# ESP12-breakout-smt-rev2.net
KiCad netlist of a schematic drawn in EAGLE
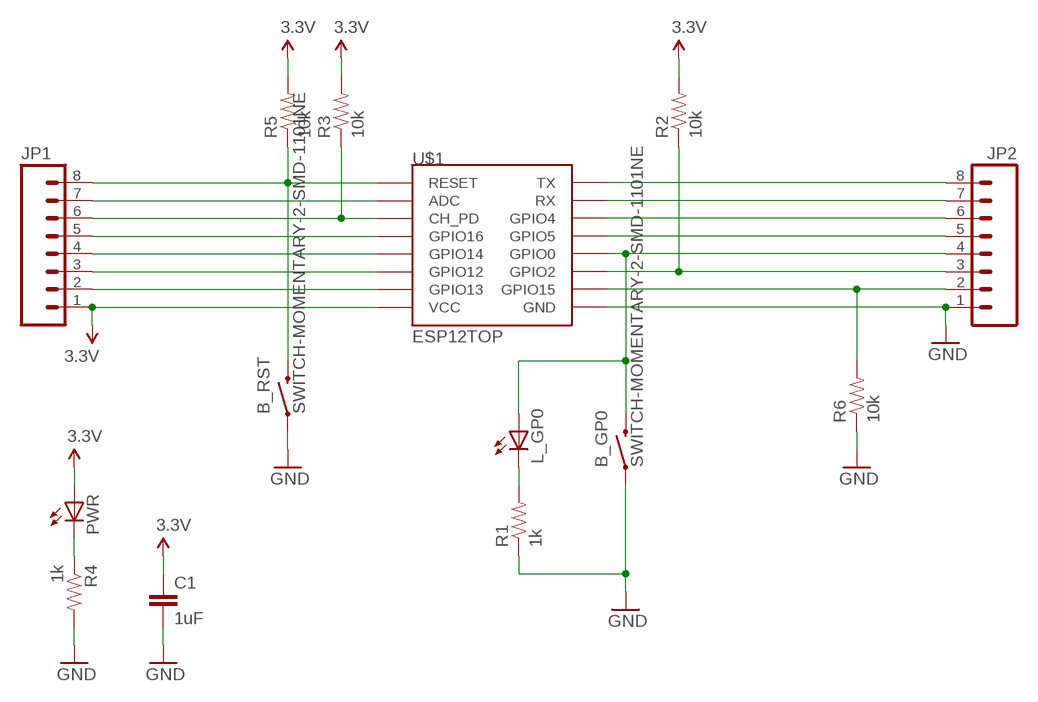
[diagram p0: schematic, sheet 1]

(export (version "E")
  (design (tool "Eeschema 10.0.6"))
  (components
    (comp (ref "B_GP0")
      (value "SWITCH-MOMENTARY-2-SMD-1101NE")
      (footprint "eagle-import:TACTILE-SWITCH-1101NE")
      (libsource (lib "eagle-import") (part "SWITCH-MOMENTARY-2-SMD-1101NE"))
    )
    (comp (ref "B_RST")
      (value "SWITCH-MOMENTARY-2-SMD-1101NE")
      (footprint "eagle-import:TACTILE-SWITCH-1101NE")
      (libsource (lib "eagle-import") (part "SWITCH-MOMENTARY-2-SMD-1101NE"))
    )
    (comp (ref "C1")
      (value "1uF")
      (footprint "eagle-import:0805")
      (libsource (lib "eagle-import") (part "CAP0805"))
    )
    (comp (ref "JP1")
      (value "M08")
      (footprint "eagle-import:1X08_PIN1_NO_SILK")
      (libsource (lib "eagle-import") (part "M08"))
    )
    (comp (ref "JP2")
      (value "M08")
      (footprint "eagle-import:1X08_PIN1_NO_SILK")
      (libsource (lib "eagle-import") (part "M08"))
    )
    (comp (ref "L_GP0")
      (value "LEDCHIPLED_0805")
      (footprint "eagle-import:CHIPLED_0805")
      (libsource (lib "eagle-import") (part "LEDCHIPLED_0805"))
    )
    (comp (ref "PWR")
      (value "LEDCHIPLED_0805")
      (footprint "eagle-import:CHIPLED_0805")
      (libsource (lib "eagle-import") (part "LEDCHIPLED_0805"))
    )
    (comp (ref "R1")
      (value "1k")
      (footprint "eagle-import:0603-RES")
      (libsource (lib "eagle-import") (part "RESISTOR0603"))
    )
    (comp (ref "R2")
      (value "10k")
      (footprint "eagle-import:0603-RES")
      (libsource (lib "eagle-import") (part "RESISTOR0603"))
    )
    (comp (ref "R3")
      (value "10k")
      (footprint "eagle-import:0603-RES")
      (libsource (lib "eagle-import") (part "RESISTOR0603"))
    )
    (comp (ref "R4")
      (value "1k")
      (footprint "eagle-import:0603-RES")
      (libsource (lib "eagle-import") (part "RESISTOR0603"))
    )
    (comp (ref "R5")
      (value "10k")
      (footprint "eagle-import:0603-RES")
      (libsource (lib "eagle-import") (part "RESISTOR0603"))
    )
    (comp (ref "R6")
      (value "10k")
      (footprint "eagle-import:0603-RES")
      (libsource (lib "eagle-import") (part "RESISTOR0603"))
    )
    (comp (ref "U$1")
      (value "ESP12TOP")
      (footprint "eagle-import:ESP12TOP")
      (libsource (lib "eagle-import") (part "ESP12TOP"))
    )
  )
  (nets
    (net (code "1") (name "3.3V") (class "Default")
      (node (ref "C1") (pin "1") (pinfunction "1_1") (pintype "passive"))
      (node (ref "JP1") (pin "1") (pinfunction "1_1") (pintype "passive"))
      (node (ref "PWR") (pin "A") (pinfunction "A_A") (pintype "passive"))
      (node (ref "R2") (pin "2") (pinfunction "2_2") (pintype "passive"))
      (node (ref "R3") (pin "2") (pinfunction "2_2") (pintype "passive"))
      (node (ref "R5") (pin "2") (pinfunction "2_2") (pintype "passive"))
      (node (ref "U$1") (pin "VCC") (pinfunction "VCC_VCC") (pintype "bidirectional"))
    )
    (net (code "2") (name "GND") (class "Default")
      (node (ref "B_GP0") (pin "1") (pinfunction "1_1") (pintype "passive"))
      (node (ref "B_RST") (pin "1") (pinfunction "1_1") (pintype "passive"))
      (node (ref "C1") (pin "2") (pinfunction "2_2") (pintype "passive"))
      (node (ref "JP2") (pin "1") (pinfunction "1_1") (pintype "passive"))
      (node (ref "R1") (pin "1") (pinfunction "1_1") (pintype "passive"))
      (node (ref "R4") (pin "2") (pinfunction "2_2") (pintype "passive"))
      (node (ref "R6") (pin "1") (pinfunction "1_1") (pintype "passive"))
      (node (ref "U$1") (pin "GND") (pinfunction "GND_GND") (pintype "bidirectional"))
    )
    (net (code "3") (name "Net-(B_GP0-Pad2)") (class "Default")
      (node (ref "B_GP0") (pin "2") (pinfunction "2_2") (pintype "passive"))
      (node (ref "JP2") (pin "4") (pinfunction "4_4") (pintype "passive"))
      (node (ref "L_GP0") (pin "A") (pinfunction "A_A") (pintype "passive"))
      (node (ref "U$1") (pin "GPIO0") (pinfunction "GPIO0_GPIO0") (pintype "bidirectional"))
    )
    (net (code "4") (name "Net-(B_RST-Pad2)") (class "Default")
      (node (ref "B_RST") (pin "2") (pinfunction "2_2") (pintype "passive"))
      (node (ref "JP1") (pin "8") (pinfunction "8_8") (pintype "passive"))
      (node (ref "R5") (pin "1") (pinfunction "1_1") (pintype "passive"))
      (node (ref "U$1") (pin "RESET") (pinfunction "RESET_RESET") (pintype "bidirectional"))
    )
    (net (code "5") (name "Net-(JP1-Pad2)") (class "Default")
      (node (ref "JP1") (pin "2") (pinfunction "2_2") (pintype "passive"))
      (node (ref "U$1") (pin "GPIO13") (pinfunction "GPIO13_GPIO13") (pintype "bidirectional"))
    )
    (net (code "6") (name "Net-(JP1-Pad3)") (class "Default")
      (node (ref "JP1") (pin "3") (pinfunction "3_3") (pintype "passive"))
      (node (ref "U$1") (pin "GPIO12") (pinfunction "GPIO12_GPIO12") (pintype "bidirectional"))
    )
    (net (code "7") (name "Net-(JP1-Pad4)") (class "Default")
      (node (ref "JP1") (pin "4") (pinfunction "4_4") (pintype "passive"))
      (node (ref "U$1") (pin "GPIO14") (pinfunction "GPIO14_GPIO14") (pintype "bidirectional"))
    )
    (net (code "8") (name "Net-(JP1-Pad5)") (class "Default")
      (node (ref "JP1") (pin "5") (pinfunction "5_5") (pintype "passive"))
      (node (ref "U$1") (pin "GPIO16") (pinfunction "GPIO16_GPIO16") (pintype "bidirectional"))
    )
    (net (code "9") (name "Net-(JP1-Pad6)") (class "Default")
      (node (ref "JP1") (pin "6") (pinfunction "6_6") (pintype "passive"))
      (node (ref "R3") (pin "1") (pinfunction "1_1") (pintype "passive"))
      (node (ref "U$1") (pin "CH_PD") (pinfunction "CH_PD_CH_PD") (pintype "bidirectional"))
    )
    (net (code "10") (name "Net-(JP1-Pad7)") (class "Default")
      (node (ref "JP1") (pin "7") (pinfunction "7_7") (pintype "passive"))
      (node (ref "U$1") (pin "ADC") (pinfunction "ADC_ADC") (pintype "bidirectional"))
    )
    (net (code "11") (name "Net-(JP2-Pad2)") (class "Default")
      (node (ref "JP2") (pin "2") (pinfunction "2_2") (pintype "passive"))
      (node (ref "R6") (pin "2") (pinfunction "2_2") (pintype "passive"))
      (node (ref "U$1") (pin "GPIO15") (pinfunction "GPIO15_GPIO15") (pintype "bidirectional"))
    )
    (net (code "12") (name "Net-(JP2-Pad3)") (class "Default")
      (node (ref "JP2") (pin "3") (pinfunction "3_3") (pintype "passive"))
      (node (ref "R2") (pin "1") (pinfunction "1_1") (pintype "passive"))
      (node (ref "U$1") (pin "GPIO2") (pinfunction "GPIO2_GPIO2") (pintype "bidirectional"))
    )
    (net (code "13") (name "Net-(JP2-Pad5)") (class "Default")
      (node (ref "JP2") (pin "5") (pinfunction "5_5") (pintype "passive"))
      (node (ref "U$1") (pin "GPIO5") (pinfunction "GPIO5_GPIO5") (pintype "bidirectional"))
    )
    (net (code "14") (name "Net-(JP2-Pad6)") (class "Default")
      (node (ref "JP2") (pin "6") (pinfunction "6_6") (pintype "passive"))
      (node (ref "U$1") (pin "GPIO4") (pinfunction "GPIO4_GPIO4") (pintype "bidirectional"))
    )
    (net (code "15") (name "Net-(L_GP0-PadC)") (class "Default")
      (node (ref "L_GP0") (pin "C") (pinfunction "C_C") (pintype "passive"))
      (node (ref "R1") (pin "2") (pinfunction "2_2") (pintype "passive"))
    )
    (net (code "16") (name "Net-(PWR-PadC)") (class "Default")
      (node (ref "PWR") (pin "C") (pinfunction "C_C") (pintype "passive"))
      (node (ref "R4") (pin "1") (pinfunction "1_1") (pintype "passive"))
    )
    (net (code "17") (name "Net-(U$1-RX)") (class "Default")
      (node (ref "JP2") (pin "7") (pinfunction "7_7") (pintype "passive"))
      (node (ref "U$1") (pin "RXD") (pinfunction "RX_RXD") (pintype "bidirectional"))
    )
    (net (code "18") (name "Net-(U$1-TX)") (class "Default")
      (node (ref "JP2") (pin "8") (pinfunction "8_8") (pintype "passive"))
      (node (ref "U$1") (pin "TXD") (pinfunction "TX_TXD") (pintype "bidirectional"))
    )
  )
)
